# RoverWing-cover-V3_0.net
KiCad netlist of a schematic drawn in EAGLE
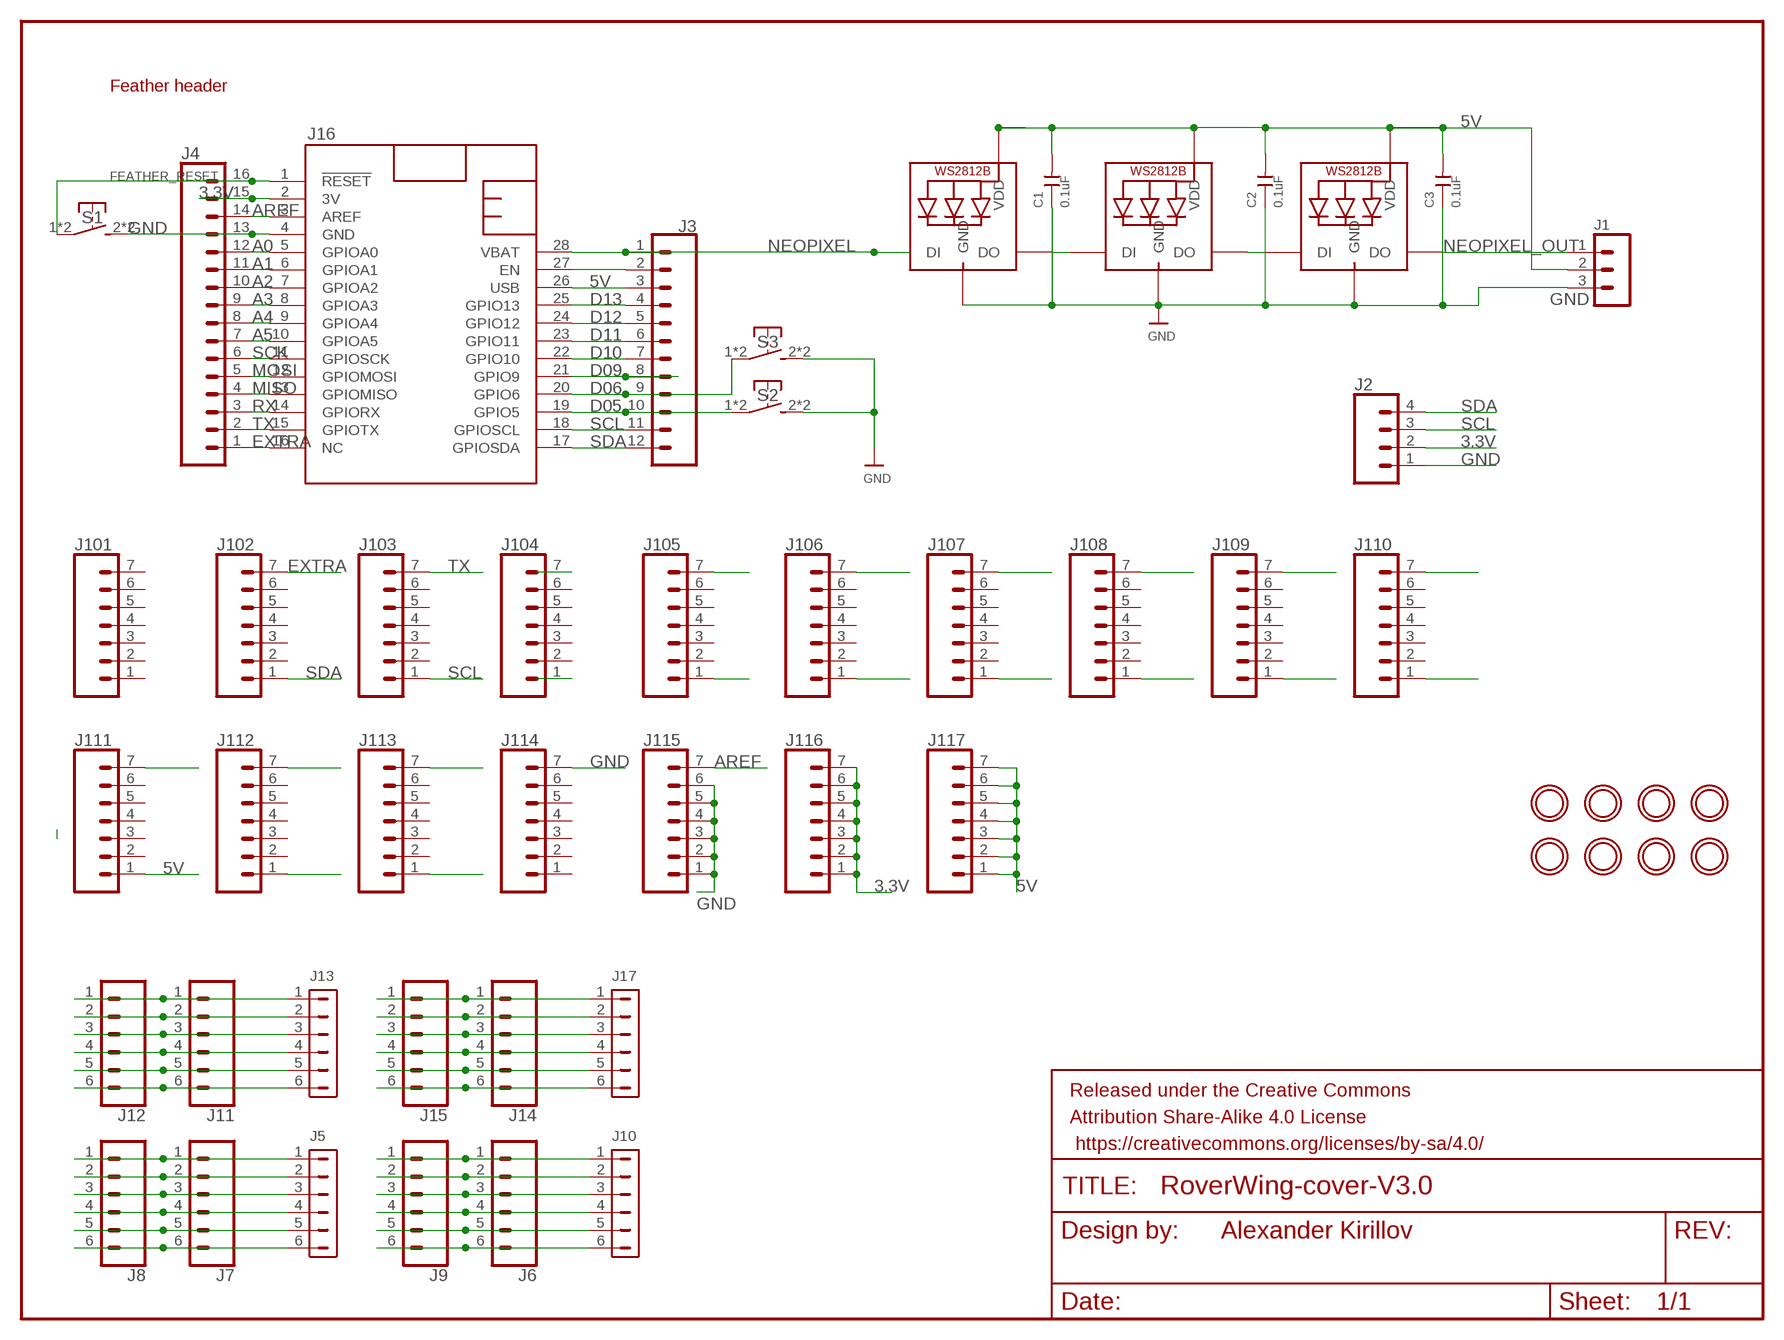
[diagram p0: schematic, sheet 1]

(export (version "E")
  (design (tool "Eeschema 10.0.6"))
  (components
    (comp (ref "C1")
      (value "0.1uF")
      (footprint "eagle-import:0603")
      (fields (field (name "MF") "AVX") (field (name "MPN") "04025C104KAT2A"))
      (libsource (lib "eagle-import") (part "CAP-CERAMIC-SMD0603"))
    )
    (comp (ref "C2")
      (value "0.1uF")
      (footprint "eagle-import:0603")
      (fields (field (name "MF") "AVX") (field (name "MPN") "04025C104KAT2A"))
      (libsource (lib "eagle-import") (part "CAP-CERAMIC-SMD0603"))
    )
    (comp (ref "C3")
      (value "0.1uF")
      (footprint "eagle-import:0603")
      (fields (field (name "MF") "AVX") (field (name "MPN") "04025C104KAT2A"))
      (libsource (lib "eagle-import") (part "CAP-CERAMIC-SMD0603"))
    )
    (comp (ref "FRAME2")
      (value "FRAME-LETTERNO_PACKAGE")
      (footprint "eagle-import:DUMMY")
      (fields (field (name "OC_NEWARK") "unknown") (field (name "DESIGNER") "Nobody"))
      (libsource (lib "eagle-import") (part "FRAME-LETTERNO_PACKAGE"))
    )
    (comp (ref "J1")
      (value "HEADER-PH-3PSIDEENTRY")
      (footprint "eagle-import:S3B-PH-K")
      (fields
        (field (name "PARTNO") "S3B-PH-K-S(LF)(SN)")
        (field (name "MF") "JST (JAPAN SOLDERLESS TERMINALS)")
        (field (name "MPN") "S3B-PH-K-S (LF)(SN)")
      )
      (libsource (lib "eagle-import") (part "HEADER-PH-3PSIDEENTRY"))
    )
    (comp (ref "J2")
      (value "CONN_04")
      (footprint "eagle-import:1X04")
      (libsource (lib "eagle-import") (part "CONN_04"))
    )
    (comp (ref "J3")
      (value "CONN_12NO_SILK")
      (footprint "eagle-import:1X12_NO_SILK")
      (libsource (lib "eagle-import") (part "CONN_12NO_SILK"))
    )
    (comp (ref "J4")
      (value "CONN_161X16_NO_SILK")
      (footprint "eagle-import:1X16_NO_SILK")
      (libsource (lib "eagle-import") (part "CONN_161X16_NO_SILK"))
    )
    (comp (ref "J5")
      (value "HEADER-PH-6PSIDEENTRY")
      (footprint "eagle-import:S6B-PH-K")
      (libsource (lib "eagle-import") (part "HEADER-PH-6PSIDEENTRY"))
    )
    (comp (ref "J6")
      (value "CONN_06NO_SILK_NO_POP")
      (footprint "eagle-import:1X06_NO_SILK")
      (libsource (lib "eagle-import") (part "CONN_06NO_SILK_NO_POP"))
    )
    (comp (ref "J7")
      (value "CONN_06NO_SILK_NO_POP")
      (footprint "eagle-import:1X06_NO_SILK")
      (libsource (lib "eagle-import") (part "CONN_06NO_SILK_NO_POP"))
    )
    (comp (ref "J8")
      (value "CONN_06NO_SILK_NO_POP")
      (footprint "eagle-import:1X06_NO_SILK")
      (libsource (lib "eagle-import") (part "CONN_06NO_SILK_NO_POP"))
    )
    (comp (ref "J9")
      (value "CONN_06NO_SILK_NO_POP")
      (footprint "eagle-import:1X06_NO_SILK")
      (libsource (lib "eagle-import") (part "CONN_06NO_SILK_NO_POP"))
    )
    (comp (ref "J10")
      (value "HEADER-PH-6PSIDEENTRY")
      (footprint "eagle-import:S6B-PH-K")
      (libsource (lib "eagle-import") (part "HEADER-PH-6PSIDEENTRY"))
    )
    (comp (ref "J11")
      (value "CONN_06NO_SILK_NO_POP")
      (footprint "eagle-import:1X06_NO_SILK")
      (libsource (lib "eagle-import") (part "CONN_06NO_SILK_NO_POP"))
    )
    (comp (ref "J12")
      (value "CONN_06NO_SILK_NO_POP")
      (footprint "eagle-import:1X06_NO_SILK")
      (libsource (lib "eagle-import") (part "CONN_06NO_SILK_NO_POP"))
    )
    (comp (ref "J13")
      (value "HEADER-PH-6PSIDEENTRY")
      (footprint "eagle-import:S6B-PH-K")
      (libsource (lib "eagle-import") (part "HEADER-PH-6PSIDEENTRY"))
    )
    (comp (ref "J14")
      (value "CONN_06NO_SILK_NO_POP")
      (footprint "eagle-import:1X06_NO_SILK")
      (libsource (lib "eagle-import") (part "CONN_06NO_SILK_NO_POP"))
    )
    (comp (ref "J15")
      (value "CONN_06NO_SILK_NO_POP")
      (footprint "eagle-import:1X06_NO_SILK")
      (libsource (lib "eagle-import") (part "CONN_06NO_SILK_NO_POP"))
    )
    (comp (ref "J16")
      (value "FEATHERWING_NODIM")
      (footprint "eagle-import:FEATHERWING_DIM")
      (libsource (lib "eagle-import") (part "FEATHERWING_NODIM"))
    )
    (comp (ref "J17")
      (value "HEADER-PH-6PSIDEENTRY")
      (footprint "eagle-import:S6B-PH-K")
      (libsource (lib "eagle-import") (part "HEADER-PH-6PSIDEENTRY"))
    )
    (comp (ref "J101")
      (value "CONN_07NO_SILK")
      (footprint "eagle-import:1X07_NO_SILK")
      (libsource (lib "eagle-import") (part "CONN_07NO_SILK"))
    )
    (comp (ref "J102")
      (value "CONN_07NO_SILK")
      (footprint "eagle-import:1X07_NO_SILK")
      (libsource (lib "eagle-import") (part "CONN_07NO_SILK"))
    )
    (comp (ref "J103")
      (value "CONN_07NO_SILK")
      (footprint "eagle-import:1X07_NO_SILK")
      (libsource (lib "eagle-import") (part "CONN_07NO_SILK"))
    )
    (comp (ref "J104")
      (value "CONN_07NO_SILK")
      (footprint "eagle-import:1X07_NO_SILK")
      (libsource (lib "eagle-import") (part "CONN_07NO_SILK"))
    )
    (comp (ref "J105")
      (value "CONN_07NO_SILK")
      (footprint "eagle-import:1X07_NO_SILK")
      (libsource (lib "eagle-import") (part "CONN_07NO_SILK"))
    )
    (comp (ref "J106")
      (value "CONN_07NO_SILK")
      (footprint "eagle-import:1X07_NO_SILK")
      (libsource (lib "eagle-import") (part "CONN_07NO_SILK"))
    )
    (comp (ref "J107")
      (value "CONN_07NO_SILK")
      (footprint "eagle-import:1X07_NO_SILK")
      (libsource (lib "eagle-import") (part "CONN_07NO_SILK"))
    )
    (comp (ref "J108")
      (value "CONN_07NO_SILK")
      (footprint "eagle-import:1X07_NO_SILK")
      (libsource (lib "eagle-import") (part "CONN_07NO_SILK"))
    )
    (comp (ref "J109")
      (value "CONN_07NO_SILK")
      (footprint "eagle-import:1X07_NO_SILK")
      (libsource (lib "eagle-import") (part "CONN_07NO_SILK"))
    )
    (comp (ref "J110")
      (value "CONN_07NO_SILK")
      (footprint "eagle-import:1X07_NO_SILK")
      (libsource (lib "eagle-import") (part "CONN_07NO_SILK"))
    )
    (comp (ref "J111")
      (value "CONN_07NO_SILK")
      (footprint "eagle-import:1X07_NO_SILK")
      (libsource (lib "eagle-import") (part "CONN_07NO_SILK"))
    )
    (comp (ref "J112")
      (value "CONN_07NO_SILK")
      (footprint "eagle-import:1X07_NO_SILK")
      (libsource (lib "eagle-import") (part "CONN_07NO_SILK"))
    )
    (comp (ref "J113")
      (value "CONN_07NO_SILK")
      (footprint "eagle-import:1X07_NO_SILK")
      (libsource (lib "eagle-import") (part "CONN_07NO_SILK"))
    )
    (comp (ref "J114")
      (value "CONN_07NO_SILK")
      (footprint "eagle-import:1X07_NO_SILK")
      (libsource (lib "eagle-import") (part "CONN_07NO_SILK"))
    )
    (comp (ref "J115")
      (value "CONN_07NO_SILK")
      (footprint "eagle-import:1X07_NO_SILK")
      (libsource (lib "eagle-import") (part "CONN_07NO_SILK"))
    )
    (comp (ref "J116")
      (value "CONN_07NO_SILK")
      (footprint "eagle-import:1X07_NO_SILK")
      (libsource (lib "eagle-import") (part "CONN_07NO_SILK"))
    )
    (comp (ref "J117")
      (value "CONN_07NO_SILK")
      (footprint "eagle-import:1X07_NO_SILK")
      (libsource (lib "eagle-import") (part "CONN_07NO_SILK"))
    )
    (comp (ref "LED1")
      (value "WS2812B3535")
      (footprint "eagle-import:LED3535")
      (fields
        (field (name "MANUFACTURER") "Worldsemi")
        (field (name "PARTNO") "WS2812B-3535 ")
        (field (name "MF") "ADAFRUIT")
      )
      (libsource (lib "eagle-import") (part "WS2812B3535"))
    )
    (comp (ref "LED2")
      (value "WS2812B3535")
      (footprint "eagle-import:LED3535")
      (fields
        (field (name "MANUFACTURER") "Worldsemi")
        (field (name "PARTNO") "WS2812B-3535 ")
        (field (name "MF") "ADAFRUIT")
      )
      (libsource (lib "eagle-import") (part "WS2812B3535"))
    )
    (comp (ref "LED3")
      (value "WS2812B3535")
      (footprint "eagle-import:LED3535")
      (fields
        (field (name "MANUFACTURER") "Worldsemi")
        (field (name "PARTNO") "WS2812B-3535 ")
        (field (name "MF") "ADAFRUIT")
      )
      (libsource (lib "eagle-import") (part "WS2812B3535"))
    )
    (comp (ref "S1")
      (value "SW-TACTILE-4.5X4.5_SMD")
      (footprint "eagle-import:TL3305")
      (fields (field (name "MF") "E-SWITCH") (field (name "MPN") "TL3305AF160QG"))
      (libsource (lib "eagle-import") (part "SW-TACTILE-4.5X4.5_SMD"))
    )
    (comp (ref "S2")
      (value "SW-TACTILE-4.5X4.5_SMD")
      (footprint "eagle-import:TL3305")
      (fields (field (name "MF") "E-SWITCH") (field (name "MPN") "TL3305AF160QG"))
      (libsource (lib "eagle-import") (part "SW-TACTILE-4.5X4.5_SMD"))
    )
    (comp (ref "S3")
      (value "SW-TACTILE-4.5X4.5_SMD")
      (footprint "eagle-import:TL3305")
      (fields (field (name "MF") "E-SWITCH") (field (name "MPN") "TL3305AF160QG"))
      (libsource (lib "eagle-import") (part "SW-TACTILE-4.5X4.5_SMD"))
    )
    (comp (ref "U$3")
      (value "MOUNTINGHOLE3.0_NPH")
      (footprint "eagle-import:MOUNTINGHOLE_3.0_NPH")
      (libsource (lib "eagle-import") (part "MOUNTINGHOLE3.0_NPH"))
    )
    (comp (ref "U$4")
      (value "MOUNTINGHOLE3.0_NPH")
      (footprint "eagle-import:MOUNTINGHOLE_3.0_NPH")
      (libsource (lib "eagle-import") (part "MOUNTINGHOLE3.0_NPH"))
    )
    (comp (ref "U$14")
      (value "MOUNTINGHOLE3.0_NPH")
      (footprint "eagle-import:MOUNTINGHOLE_3.0_NPH")
      (libsource (lib "eagle-import") (part "MOUNTINGHOLE3.0_NPH"))
    )
    (comp (ref "U$15")
      (value "MOUNTINGHOLE3.0_NPH")
      (footprint "eagle-import:MOUNTINGHOLE_3.0_NPH")
      (libsource (lib "eagle-import") (part "MOUNTINGHOLE3.0_NPH"))
    )
    (comp (ref "U$24")
      (value "MOUNTINGHOLE3.0_NPH")
      (footprint "eagle-import:MOUNTINGHOLE_3.0_NPH")
      (libsource (lib "eagle-import") (part "MOUNTINGHOLE3.0_NPH"))
    )
    (comp (ref "U$25")
      (value "MOUNTINGHOLE3.0_NPH")
      (footprint "eagle-import:MOUNTINGHOLE_3.0_NPH")
      (libsource (lib "eagle-import") (part "MOUNTINGHOLE3.0_NPH"))
    )
    (comp (ref "U$26")
      (value "MOUNTINGHOLE3.0_NPH")
      (footprint "eagle-import:MOUNTINGHOLE_3.0_NPH")
      (libsource (lib "eagle-import") (part "MOUNTINGHOLE3.0_NPH"))
    )
    (comp (ref "U$27")
      (value "MOUNTINGHOLE3.0_NPH")
      (footprint "eagle-import:MOUNTINGHOLE_3.0_NPH")
      (libsource (lib "eagle-import") (part "MOUNTINGHOLE3.0_NPH"))
    )
  )
  (nets
    (net (code "1") (name "/3.3V") (class "Default")
      (node (ref "J116") (pin "1") (pinfunction "1_1") (pintype "passive"))
      (node (ref "J116") (pin "2") (pinfunction "2_2") (pintype "passive"))
      (node (ref "J116") (pin "3") (pinfunction "3_3") (pintype "passive"))
      (node (ref "J116") (pin "4") (pinfunction "4_4") (pintype "passive"))
      (node (ref "J116") (pin "5") (pinfunction "5_5") (pintype "passive"))
      (node (ref "J116") (pin "6") (pinfunction "6_6") (pintype "passive"))
      (node (ref "J116") (pin "7") (pinfunction "7_7") (pintype "passive"))
      (node (ref "J16") (pin "2") (pinfunction "3V_2") (pintype "power_in"))
      (node (ref "J2") (pin "2") (pinfunction "2_2") (pintype "passive"))
      (node (ref "J4") (pin "15") (pinfunction "15_15") (pintype "passive"))
    )
    (net (code "2") (name "/5V") (class "Default")
      (node (ref "C1") (pin "2") (pinfunction "2_2") (pintype "passive"))
      (node (ref "C2") (pin "2") (pinfunction "2_2") (pintype "passive"))
      (node (ref "C3") (pin "2") (pinfunction "2_2") (pintype "passive"))
      (node (ref "J1") (pin "2") (pinfunction "2_2") (pintype "passive"))
      (node (ref "J111") (pin "1") (pinfunction "1_1") (pintype "passive"))
      (node (ref "J117") (pin "1") (pinfunction "1_1") (pintype "passive"))
      (node (ref "J117") (pin "2") (pinfunction "2_2") (pintype "passive"))
      (node (ref "J117") (pin "3") (pinfunction "3_3") (pintype "passive"))
      (node (ref "J117") (pin "4") (pinfunction "4_4") (pintype "passive"))
      (node (ref "J117") (pin "5") (pinfunction "5_5") (pintype "passive"))
      (node (ref "J117") (pin "6") (pinfunction "6_6") (pintype "passive"))
      (node (ref "J117") (pin "7") (pinfunction "7_7") (pintype "passive"))
      (node (ref "J16") (pin "26") (pinfunction "USB_26") (pintype "power_in"))
      (node (ref "J3") (pin "3") (pinfunction "3_3") (pintype "passive"))
      (node (ref "LED1") (pin "3") (pinfunction "VDD_3") (pintype "power_in"))
      (node (ref "LED2") (pin "3") (pinfunction "VDD_3") (pintype "power_in"))
      (node (ref "LED3") (pin "3") (pinfunction "VDD_3") (pintype "power_in"))
    )
    (net (code "3") (name "/A0") (class "Default")
      (node (ref "J113") (pin "7") (pinfunction "7_7") (pintype "passive"))
      (node (ref "J16") (pin "5") (pinfunction "GPIOA0_5") (pintype "bidirectional"))
      (node (ref "J4") (pin "12") (pinfunction "12_12") (pintype "passive"))
    )
    (net (code "4") (name "/A1") (class "Default")
      (node (ref "J112") (pin "7") (pinfunction "7_7") (pintype "passive"))
      (node (ref "J16") (pin "6") (pinfunction "GPIOA1_6") (pintype "bidirectional"))
      (node (ref "J4") (pin "11") (pinfunction "11_11") (pintype "passive"))
    )
    (net (code "5") (name "/A2") (class "Default")
      (node (ref "J111") (pin "7") (pinfunction "7_7") (pintype "passive"))
      (node (ref "J16") (pin "7") (pinfunction "GPIOA2_7") (pintype "bidirectional"))
      (node (ref "J4") (pin "10") (pinfunction "10_10") (pintype "passive"))
    )
    (net (code "6") (name "/A3") (class "Default")
      (node (ref "J110") (pin "7") (pinfunction "7_7") (pintype "passive"))
      (node (ref "J16") (pin "8") (pinfunction "GPIOA3_8") (pintype "bidirectional"))
      (node (ref "J4") (pin "9") (pinfunction "9_9") (pintype "passive"))
    )
    (net (code "7") (name "/A4") (class "Default")
      (node (ref "J109") (pin "7") (pinfunction "7_7") (pintype "passive"))
      (node (ref "J16") (pin "9") (pinfunction "GPIOA4_9") (pintype "bidirectional"))
      (node (ref "J4") (pin "8") (pinfunction "8_8") (pintype "passive"))
    )
    (net (code "8") (name "/A5") (class "Default")
      (node (ref "J108") (pin "7") (pinfunction "7_7") (pintype "passive"))
      (node (ref "J16") (pin "10") (pinfunction "GPIOA5_10") (pintype "bidirectional"))
      (node (ref "J4") (pin "7") (pinfunction "7_7") (pintype "passive"))
    )
    (net (code "9") (name "/AREF") (class "Default")
      (node (ref "J115") (pin "7") (pinfunction "7_7") (pintype "passive"))
      (node (ref "J16") (pin "3") (pinfunction "AREF_3") (pintype "passive"))
      (node (ref "J4") (pin "14") (pinfunction "14_14") (pintype "passive"))
    )
    (net (code "10") (name "/D05") (class "Default")
      (node (ref "J104") (pin "1") (pinfunction "1_1") (pintype "passive"))
      (node (ref "J16") (pin "19") (pinfunction "GPIO5_19") (pintype "bidirectional"))
      (node (ref "J3") (pin "10") (pinfunction "10_10") (pintype "passive"))
      (node (ref "S2") (pin "1") (pinfunction "P1_1") (pintype "passive"))
      (node (ref "S2") (pin "4") (pinfunction "P1_4") (pintype "passive"))
    )
    (net (code "11") (name "/D06") (class "Default")
      (node (ref "J105") (pin "1") (pinfunction "1_1") (pintype "passive"))
      (node (ref "J16") (pin "20") (pinfunction "GPIO6_20") (pintype "bidirectional"))
      (node (ref "J3") (pin "9") (pinfunction "9_9") (pintype "passive"))
      (node (ref "S3") (pin "1") (pinfunction "P1_1") (pintype "passive"))
      (node (ref "S3") (pin "4") (pinfunction "P1_4") (pintype "passive"))
    )
    (net (code "12") (name "/D09") (class "Default")
      (node (ref "J106") (pin "1") (pinfunction "1_1") (pintype "passive"))
      (node (ref "J16") (pin "21") (pinfunction "GPIO9_21") (pintype "bidirectional"))
      (node (ref "J3") (pin "8") (pinfunction "8_8") (pintype "passive"))
    )
    (net (code "13") (name "/D10") (class "Default")
      (node (ref "J107") (pin "1") (pinfunction "1_1") (pintype "passive"))
      (node (ref "J16") (pin "22") (pinfunction "GPIO10_22") (pintype "bidirectional"))
      (node (ref "J3") (pin "7") (pinfunction "7_7") (pintype "passive"))
    )
    (net (code "14") (name "/D11") (class "Default")
      (node (ref "J108") (pin "1") (pinfunction "1_1") (pintype "passive"))
      (node (ref "J16") (pin "23") (pinfunction "GPIO11_23") (pintype "bidirectional"))
      (node (ref "J3") (pin "6") (pinfunction "6_6") (pintype "passive"))
    )
    (net (code "15") (name "/D12") (class "Default")
      (node (ref "J109") (pin "1") (pinfunction "1_1") (pintype "passive"))
      (node (ref "J16") (pin "24") (pinfunction "GPIO12_24") (pintype "bidirectional"))
      (node (ref "J3") (pin "5") (pinfunction "5_5") (pintype "passive"))
    )
    (net (code "16") (name "/D13") (class "Default")
      (node (ref "J110") (pin "1") (pinfunction "1_1") (pintype "passive"))
      (node (ref "J16") (pin "25") (pinfunction "GPIO13_25") (pintype "bidirectional"))
      (node (ref "J3") (pin "4") (pinfunction "4_4") (pintype "passive"))
    )
    (net (code "17") (name "/EXTRA") (class "Default")
      (node (ref "J102") (pin "7") (pinfunction "7_7") (pintype "passive"))
      (node (ref "J16") (pin "16") (pinfunction "NC_16") (pintype "passive"))
      (node (ref "J4") (pin "1") (pinfunction "1_1") (pintype "passive"))
    )
    (net (code "18") (name "/FEATHER_RESET") (class "Default")
      (node (ref "J16") (pin "1") (pinfunction "~{RESET}_1") (pintype "input"))
      (node (ref "J4") (pin "16") (pinfunction "16_16") (pintype "passive"))
      (node (ref "S1") (pin "1") (pinfunction "P1_1") (pintype "passive"))
      (node (ref "S1") (pin "4") (pinfunction "P1_4") (pintype "passive"))
    )
    (net (code "19") (name "/MISO") (class "Default")
      (node (ref "J105") (pin "7") (pinfunction "7_7") (pintype "passive"))
      (node (ref "J16") (pin "13") (pinfunction "GPIOMISO_13") (pintype "bidirectional"))
      (node (ref "J4") (pin "4") (pinfunction "4_4") (pintype "passive"))
    )
    (net (code "20") (name "/MOSI") (class "Default")
      (node (ref "J106") (pin "7") (pinfunction "7_7") (pintype "passive"))
      (node (ref "J16") (pin "12") (pinfunction "GPIOMOSI_12") (pintype "bidirectional"))
      (node (ref "J4") (pin "5") (pinfunction "5_5") (pintype "passive"))
    )
    (net (code "21") (name "/N$37") (class "Default")
      (node (ref "J112") (pin "1") (pinfunction "1_1") (pintype "passive"))
      (node (ref "J16") (pin "27") (pinfunction "EN_27") (pintype "passive"))
      (node (ref "J3") (pin "2") (pinfunction "2_2") (pintype "passive"))
    )
    (net (code "22") (name "/NEOPIXEL") (class "Default")
      (node (ref "J16") (pin "28") (pinfunction "VBAT_28") (pintype "power_in"))
      (node (ref "J3") (pin "1") (pinfunction "1_1") (pintype "passive"))
      (node (ref "LED1") (pin "2") (pinfunction "DI_2") (pintype "input"))
    )
    (net (code "23") (name "/NEOPIXEL_OUT") (class "Default")
      (node (ref "J1") (pin "1") (pinfunction "1_1") (pintype "passive"))
      (node (ref "LED3") (pin "4") (pinfunction "DO_4") (pintype "output"))
    )
    (net (code "24") (name "/RX") (class "Default")
      (node (ref "J104") (pin "7") (pinfunction "7_7") (pintype "passive"))
      (node (ref "J16") (pin "14") (pinfunction "GPIORX_14") (pintype "bidirectional"))
      (node (ref "J4") (pin "3") (pinfunction "3_3") (pintype "passive"))
    )
    (net (code "25") (name "/SCK") (class "Default")
      (node (ref "J107") (pin "7") (pinfunction "7_7") (pintype "passive"))
      (node (ref "J16") (pin "11") (pinfunction "GPIOSCK_11") (pintype "bidirectional"))
      (node (ref "J4") (pin "6") (pinfunction "6_6") (pintype "passive"))
    )
    (net (code "26") (name "/SCL") (class "Default")
      (node (ref "J103") (pin "1") (pinfunction "1_1") (pintype "passive"))
      (node (ref "J16") (pin "18") (pinfunction "GPIOSCL_18") (pintype "bidirectional"))
      (node (ref "J2") (pin "3") (pinfunction "3_3") (pintype "passive"))
      (node (ref "J3") (pin "11") (pinfunction "11_11") (pintype "passive"))
    )
    (net (code "27") (name "/SDA") (class "Default")
      (node (ref "J102") (pin "1") (pinfunction "1_1") (pintype "passive"))
      (node (ref "J16") (pin "17") (pinfunction "GPIOSDA_17") (pintype "bidirectional"))
      (node (ref "J2") (pin "4") (pinfunction "4_4") (pintype "passive"))
      (node (ref "J3") (pin "12") (pinfunction "12_12") (pintype "passive"))
    )
    (net (code "28") (name "/TX") (class "Default")
      (node (ref "J103") (pin "7") (pinfunction "7_7") (pintype "passive"))
      (node (ref "J16") (pin "15") (pinfunction "GPIOTX_15") (pintype "bidirectional"))
      (node (ref "J4") (pin "2") (pinfunction "2_2") (pintype "passive"))
    )
    (net (code "29") (name "GND") (class "Default")
      (node (ref "C1") (pin "1") (pinfunction "1_1") (pintype "passive"))
      (node (ref "C2") (pin "1") (pinfunction "1_1") (pintype "passive"))
      (node (ref "C3") (pin "1") (pinfunction "1_1") (pintype "passive"))
      (node (ref "J1") (pin "3") (pinfunction "3_3") (pintype "passive"))
      (node (ref "J114") (pin "7") (pinfunction "7_7") (pintype "passive"))
      (node (ref "J115") (pin "1") (pinfunction "1_1") (pintype "passive"))
      (node (ref "J115") (pin "2") (pinfunction "2_2") (pintype "passive"))
      (node (ref "J115") (pin "3") (pinfunction "3_3") (pintype "passive"))
      (node (ref "J115") (pin "4") (pinfunction "4_4") (pintype "passive"))
      (node (ref "J115") (pin "5") (pinfunction "5_5") (pintype "passive"))
      (node (ref "J115") (pin "6") (pinfunction "6_6") (pintype "passive"))
      (node (ref "J16") (pin "4") (pinfunction "GND_4") (pintype "power_in"))
      (node (ref "J2") (pin "1") (pinfunction "1_1") (pintype "passive"))
      (node (ref "J4") (pin "13") (pinfunction "13_13") (pintype "passive"))
      (node (ref "LED1") (pin "1") (pinfunction "GND_1") (pintype "power_in"))
      (node (ref "LED2") (pin "1") (pinfunction "GND_1") (pintype "power_in"))
      (node (ref "LED3") (pin "1") (pinfunction "GND_1") (pintype "power_in"))
      (node (ref "S1") (pin "2") (pinfunction "S1_2") (pintype "passive"))
      (node (ref "S1") (pin "3") (pinfunction "S1_3") (pintype "passive"))
      (node (ref "S2") (pin "2") (pinfunction "S1_2") (pintype "passive"))
      (node (ref "S2") (pin "3") (pinfunction "S1_3") (pintype "passive"))
      (node (ref "S3") (pin "2") (pinfunction "S1_2") (pintype "passive"))
      (node (ref "S3") (pin "3") (pinfunction "S1_3") (pintype "passive"))
    )
    (net (code "30") (name "Net-(J5-Pad1)") (class "Default")
      (node (ref "J5") (pin "1") (pinfunction "1_1") (pintype "passive"))
      (node (ref "J7") (pin "1") (pinfunction "1_1") (pintype "passive"))
      (node (ref "J8") (pin "1") (pinfunction "1_1") (pintype "passive"))
    )
    (net (code "31") (name "Net-(J5-Pad2)") (class "Default")
      (node (ref "J5") (pin "2") (pinfunction "2_2") (pintype "passive"))
      (node (ref "J7") (pin "2") (pinfunction "2_2") (pintype "passive"))
      (node (ref "J8") (pin "2") (pinfunction "2_2") (pintype "passive"))
    )
    (net (code "32") (name "Net-(J5-Pad3)") (class "Default")
      (node (ref "J5") (pin "3") (pinfunction "3_3") (pintype "passive"))
      (node (ref "J7") (pin "3") (pinfunction "3_3") (pintype "passive"))
      (node (ref "J8") (pin "3") (pinfunction "3_3") (pintype "passive"))
    )
    (net (code "33") (name "Net-(J5-Pad4)") (class "Default")
      (node (ref "J5") (pin "4") (pinfunction "4_4") (pintype "passive"))
      (node (ref "J7") (pin "4") (pinfunction "4_4") (pintype "passive"))
      (node (ref "J8") (pin "4") (pinfunction "4_4") (pintype "passive"))
    )
    (net (code "34") (name "Net-(J5-Pad5)") (class "Default")
      (node (ref "J5") (pin "5") (pinfunction "5_5") (pintype "passive"))
      (node (ref "J7") (pin "5") (pinfunction "5_5") (pintype "passive"))
      (node (ref "J8") (pin "5") (pinfunction "5_5") (pintype "passive"))
    )
    (net (code "35") (name "Net-(J5-Pad6)") (class "Default")
      (node (ref "J5") (pin "6") (pinfunction "6_6") (pintype "passive"))
      (node (ref "J7") (pin "6") (pinfunction "6_6") (pintype "passive"))
      (node (ref "J8") (pin "6") (pinfunction "6_6") (pintype "passive"))
    )
    (net (code "36") (name "Net-(J10-Pad1)") (class "Default")
      (node (ref "J10") (pin "1") (pinfunction "1_1") (pintype "passive"))
      (node (ref "J6") (pin "1") (pinfunction "1_1") (pintype "passive"))
      (node (ref "J9") (pin "1") (pinfunction "1_1") (pintype "passive"))
    )
    (net (code "37") (name "Net-(J10-Pad2)") (class "Default")
      (node (ref "J10") (pin "2") (pinfunction "2_2") (pintype "passive"))
      (node (ref "J6") (pin "2") (pinfunction "2_2") (pintype "passive"))
      (node (ref "J9") (pin "2") (pinfunction "2_2") (pintype "passive"))
    )
    (net (code "38") (name "Net-(J10-Pad3)") (class "Default")
      (node (ref "J10") (pin "3") (pinfunction "3_3") (pintype "passive"))
      (node (ref "J6") (pin "3") (pinfunction "3_3") (pintype "passive"))
      (node (ref "J9") (pin "3") (pinfunction "3_3") (pintype "passive"))
    )
    (net (code "39") (name "Net-(J10-Pad4)") (class "Default")
      (node (ref "J10") (pin "4") (pinfunction "4_4") (pintype "passive"))
      (node (ref "J6") (pin "4") (pinfunction "4_4") (pintype "passive"))
      (node (ref "J9") (pin "4") (pinfunction "4_4") (pintype "passive"))
    )
    (net (code "40") (name "Net-(J10-Pad5)") (class "Default")
      (node (ref "J10") (pin "5") (pinfunction "5_5") (pintype "passive"))
      (node (ref "J6") (pin "5") (pinfunction "5_5") (pintype "passive"))
      (node (ref "J9") (pin "5") (pinfunction "5_5") (pintype "passive"))
    )
    (net (code "41") (name "Net-(J10-Pad6)") (class "Default")
      (node (ref "J10") (pin "6") (pinfunction "6_6") (pintype "passive"))
      (node (ref "J6") (pin "6") (pinfunction "6_6") (pintype "passive"))
      (node (ref "J9") (pin "6") (pinfunction "6_6") (pintype "passive"))
    )
    (net (code "42") (name "Net-(J11-Pad1)") (class "Default")
      (node (ref "J11") (pin "1") (pinfunction "1_1") (pintype "passive"))
      (node (ref "J12") (pin "1") (pinfunction "1_1") (pintype "passive"))
      (node (ref "J13") (pin "1") (pinfunction "1_1") (pintype "passive"))
    )
    (net (code "43") (name "Net-(J11-Pad2)") (class "Default")
      (node (ref "J11") (pin "2") (pinfunction "2_2") (pintype "passive"))
      (node (ref "J12") (pin "2") (pinfunction "2_2") (pintype "passive"))
      (node (ref "J13") (pin "2") (pinfunction "2_2") (pintype "passive"))
    )
    (net (code "44") (name "Net-(J11-Pad3)") (class "Default")
      (node (ref "J11") (pin "3") (pinfunction "3_3") (pintype "passive"))
      (node (ref "J12") (pin "3") (pinfunction "3_3") (pintype "passive"))
      (node (ref "J13") (pin "3") (pinfunction "3_3") (pintype "passive"))
    )
    (net (code "45") (name "Net-(J11-Pad4)") (class "Default")
      (node (ref "J11") (pin "4") (pinfunction "4_4") (pintype "passive"))
      (node (ref "J12") (pin "4") (pinfunction "4_4") (pintype "passive"))
      (node (ref "J13") (pin "4") (pinfunction "4_4") (pintype "passive"))
    )
    (net (code "46") (name "Net-(J11-Pad5)") (class "Default")
      (node (ref "J11") (pin "5") (pinfunction "5_5") (pintype "passive"))
      (node (ref "J12") (pin "5") (pinfunction "5_5") (pintype "passive"))
      (node (ref "J13") (pin "5") (pinfunction "5_5") (pintype "passive"))
    )
    (net (code "47") (name "Net-(J11-Pad6)") (class "Default")
      (node (ref "J11") (pin "6") (pinfunction "6_6") (pintype "passive"))
      (node (ref "J12") (pin "6") (pinfunction "6_6") (pintype "passive"))
      (node (ref "J13") (pin "6") (pinfunction "6_6") (pintype "passive"))
    )
    (net (code "48") (name "Net-(J14-Pad1)") (class "Default")
      (node (ref "J14") (pin "1") (pinfunction "1_1") (pintype "passive"))
      (node (ref "J15") (pin "1") (pinfunction "1_1") (pintype "passive"))
      (node (ref "J17") (pin "1") (pinfunction "1_1") (pintype "passive"))
    )
    (net (code "49") (name "Net-(J14-Pad2)") (class "Default")
      (node (ref "J14") (pin "2") (pinfunction "2_2") (pintype "passive"))
      (node (ref "J15") (pin "2") (pinfunction "2_2") (pintype "passive"))
      (node (ref "J17") (pin "2") (pinfunction "2_2") (pintype "passive"))
    )
    (net (code "50") (name "Net-(J14-Pad3)") (class "Default")
      (node (ref "J14") (pin "3") (pinfunction "3_3") (pintype "passive"))
      (node (ref "J15") (pin "3") (pinfunction "3_3") (pintype "passive"))
      (node (ref "J17") (pin "3") (pinfunction "3_3") (pintype "passive"))
    )
    (net (code "51") (name "Net-(J14-Pad4)") (class "Default")
      (node (ref "J14") (pin "4") (pinfunction "4_4") (pintype "passive"))
      (node (ref "J15") (pin "4") (pinfunction "4_4") (pintype "passive"))
      (node (ref "J17") (pin "4") (pinfunction "4_4") (pintype "passive"))
    )
    (net (code "52") (name "Net-(J14-Pad5)") (class "Default")
      (node (ref "J14") (pin "5") (pinfunction "5_5") (pintype "passive"))
      (node (ref "J15") (pin "5") (pinfunction "5_5") (pintype "passive"))
      (node (ref "J17") (pin "5") (pinfunction "5_5") (pintype "passive"))
    )
    (net (code "53") (name "Net-(J14-Pad6)") (class "Default")
      (node (ref "J14") (pin "6") (pinfunction "6_6") (pintype "passive"))
      (node (ref "J15") (pin "6") (pinfunction "6_6") (pintype "passive"))
      (node (ref "J17") (pin "6") (pinfunction "6_6") (pintype "passive"))
    )
    (net (code "54") (name "Net-(LED1-DO)") (class "Default")
      (node (ref "LED1") (pin "4") (pinfunction "DO_4") (pintype "output"))
      (node (ref "LED2") (pin "2") (pinfunction "DI_2") (pintype "input"))
    )
    (net (code "55") (name "Net-(LED2-DO)") (class "Default")
      (node (ref "LED2") (pin "4") (pinfunction "DO_4") (pintype "output"))
      (node (ref "LED3") (pin "2") (pinfunction "DI_2") (pintype "input"))
    )
    (net (code "56") (name "unconnected-(J101-Pad1)") (class "Default")
      (node (ref "J101") (pin "1") (pinfunction "1_1") (pintype "passive"))
    )
    (net (code "57") (name "unconnected-(J101-Pad2)") (class "Default")
      (node (ref "J101") (pin "2") (pinfunction "2_2") (pintype "passive"))
    )
    (net (code "58") (name "unconnected-(J101-Pad3)") (class "Default")
      (node (ref "J101") (pin "3") (pinfunction "3_3") (pintype "passive"))
    )
    (net (code "59") (name "unconnected-(J101-Pad4)") (class "Default")
      (node (ref "J101") (pin "4") (pinfunction "4_4") (pintype "passive"))
    )
    (net (code "60") (name "unconnected-(J101-Pad5)") (class "Default")
      (node (ref "J101") (pin "5") (pinfunction "5_5") (pintype "passive"))
    )
    (net (code "61") (name "unconnected-(J101-Pad6)") (class "Default")
      (node (ref "J101") (pin "6") (pinfunction "6_6") (pintype "passive"))
    )
    (net (code "62") (name "unconnected-(J101-Pad7)") (class "Default")
      (node (ref "J101") (pin "7") (pinfunction "7_7") (pintype "passive"))
    )
    (net (code "63") (name "unconnected-(J102-Pad2)") (class "Default")
      (node (ref "J102") (pin "2") (pinfunction "2_2") (pintype "passive"))
    )
    (net (code "64") (name "unconnected-(J102-Pad3)") (class "Default")
      (node (ref "J102") (pin "3") (pinfunction "3_3") (pintype "passive"))
    )
    (net (code "65") (name "unconnected-(J102-Pad4)") (class "Default")
      (node (ref "J102") (pin "4") (pinfunction "4_4") (pintype "passive"))
    )
    (net (code "66") (name "unconnected-(J102-Pad5)") (class "Default")
      (node (ref "J102") (pin "5") (pinfunction "5_5") (pintype "passive"))
    )
    (net (code "67") (name "unconnected-(J102-Pad6)") (class "Default")
      (node (ref "J102") (pin "6") (pinfunction "6_6") (pintype "passive"))
    )
    (net (code "68") (name "unconnected-(J103-Pad2)") (class "Default")
      (node (ref "J103") (pin "2") (pinfunction "2_2") (pintype "passive"))
    )
    (net (code "69") (name "unconnected-(J103-Pad3)") (class "Default")
      (node (ref "J103") (pin "3") (pinfunction "3_3") (pintype "passive"))
    )
    (net (code "70") (name "unconnected-(J103-Pad4)") (class "Default")
      (node (ref "J103") (pin "4") (pinfunction "4_4") (pintype "passive"))
    )
    (net (code "71") (name "unconnected-(J103-Pad5)") (class "Default")
      (node (ref "J103") (pin "5") (pinfunction "5_5") (pintype "passive"))
    )
    (net (code "72") (name "unconnected-(J103-Pad6)") (class "Default")
      (node (ref "J103") (pin "6") (pinfunction "6_6") (pintype "passive"))
    )
    (net (code "73") (name "unconnected-(J104-Pad2)") (class "Default")
      (node (ref "J104") (pin "2") (pinfunction "2_2") (pintype "passive"))
    )
    (net (code "74") (name "unconnected-(J104-Pad3)") (class "Default")
      (node (ref "J104") (pin "3") (pinfunction "3_3") (pintype "passive"))
    )
    (net (code "75") (name "unconnected-(J104-Pad4)") (class "Default")
      (node (ref "J104") (pin "4") (pinfunction "4_4") (pintype "passive"))
    )
    (net (code "76") (name "unconnected-(J104-Pad5)") (class "Default")
      (node (ref "J104") (pin "5") (pinfunction "5_5") (pintype "passive"))
    )
    (net (code "77") (name "unconnected-(J104-Pad6)") (class "Default")
      (node (ref "J104") (pin "6") (pinfunction "6_6") (pintype "passive"))
    )
    (net (code "78") (name "unconnected-(J105-Pad2)") (class "Default")
      (node (ref "J105") (pin "2") (pinfunction "2_2") (pintype "passive"))
    )
    (net (code "79") (name "unconnected-(J105-Pad3)") (class "Default")
      (node (ref "J105") (pin "3") (pinfunction "3_3") (pintype "passive"))
    )
    (net (code "80") (name "unconnected-(J105-Pad4)") (class "Default")
      (node (ref "J105") (pin "4") (pinfunction "4_4") (pintype "passive"))
    )
    (net (code "81") (name "unconnected-(J105-Pad5)") (class "Default")
      (node (ref "J105") (pin "5") (pinfunction "5_5") (pintype "passive"))
    )
    (net (code "82") (name "unconnected-(J105-Pad6)") (class "Default")
      (node (ref "J105") (pin "6") (pinfunction "6_6") (pintype "passive"))
    )
    (net (code "83") (name "unconnected-(J106-Pad2)") (class "Default")
      (node (ref "J106") (pin "2") (pinfunction "2_2") (pintype "passive"))
    )
    (net (code "84") (name "unconnected-(J106-Pad3)") (class "Default")
      (node (ref "J106") (pin "3") (pinfunction "3_3") (pintype "passive"))
    )
    (net (code "85") (name "unconnected-(J106-Pad4)") (class "Default")
      (node (ref "J106") (pin "4") (pinfunction "4_4") (pintype "passive"))
    )
    (net (code "86") (name "unconnected-(J106-Pad5)") (class "Default")
      (node (ref "J106") (pin "5") (pinfunction "5_5") (pintype "passive"))
    )
    (net (code "87") (name "unconnected-(J106-Pad6)") (class "Default")
      (node (ref "J106") (pin "6") (pinfunction "6_6") (pintype "passive"))
    )
    (net (code "88") (name "unconnected-(J107-Pad2)") (class "Default")
      (node (ref "J107") (pin "2") (pinfunction "2_2") (pintype "passive"))
    )
    (net (code "89") (name "unconnected-(J107-Pad3)") (class "Default")
      (node (ref "J107") (pin "3") (pinfunction "3_3") (pintype "passive"))
    )
    (net (code "90") (name "unconnected-(J107-Pad4)") (class "Default")
      (node (ref "J107") (pin "4") (pinfunction "4_4") (pintype "passive"))
    )
    (net (code "91") (name "unconnected-(J107-Pad5)") (class "Default")
      (node (ref "J107") (pin "5") (pinfunction "5_5") (pintype "passive"))
    )
    (net (code "92") (name "unconnected-(J107-Pad6)") (class "Default")
      (node (ref "J107") (pin "6") (pinfunction "6_6") (pintype "passive"))
    )
    (net (code "93") (name "unconnected-(J108-Pad2)") (class "Default")
      (node (ref "J108") (pin "2") (pinfunction "2_2") (pintype "passive"))
    )
    (net (code "94") (name "unconnected-(J108-Pad3)") (class "Default")
      (node (ref "J108") (pin "3") (pinfunction "3_3") (pintype "passive"))
    )
    (net (code "95") (name "unconnected-(J108-Pad4)") (class "Default")
      (node (ref "J108") (pin "4") (pinfunction "4_4") (pintype "passive"))
    )
    (net (code "96") (name "unconnected-(J108-Pad5)") (class "Default")
      (node (ref "J108") (pin "5") (pinfunction "5_5") (pintype "passive"))
    )
    (net (code "97") (name "unconnected-(J108-Pad6)") (class "Default")
      (node (ref "J108") (pin "6") (pinfunction "6_6") (pintype "passive"))
    )
    (net (code "98") (name "unconnected-(J109-Pad2)") (class "Default")
      (node (ref "J109") (pin "2") (pinfunction "2_2") (pintype "passive"))
    )
    (net (code "99") (name "unconnected-(J109-Pad3)") (class "Default")
      (node (ref "J109") (pin "3") (pinfunction "3_3") (pintype "passive"))
    )
    (net (code "100") (name "unconnected-(J109-Pad4)") (class "Default")
      (node (ref "J109") (pin "4") (pinfunction "4_4") (pintype "passive"))
    )
    (net (code "101") (name "unconnected-(J109-Pad5)") (class "Default")
      (node (ref "J109") (pin "5") (pinfunction "5_5") (pintype "passive"))
    )
    (net (code "102") (name "unconnected-(J109-Pad6)") (class "Default")
      (node (ref "J109") (pin "6") (pinfunction "6_6") (pintype "passive"))
    )
    (net (code "103") (name "unconnected-(J110-Pad2)") (class "Default")
      (node (ref "J110") (pin "2") (pinfunction "2_2") (pintype "passive"))
    )
    (net (code "104") (name "unconnected-(J110-Pad3)") (class "Default")
      (node (ref "J110") (pin "3") (pinfunction "3_3") (pintype "passive"))
    )
    (net (code "105") (name "unconnected-(J110-Pad4)") (class "Default")
      (node (ref "J110") (pin "4") (pinfunction "4_4") (pintype "passive"))
    )
    (net (code "106") (name "unconnected-(J110-Pad5)") (class "Default")
      (node (ref "J110") (pin "5") (pinfunction "5_5") (pintype "passive"))
    )
    (net (code "107") (name "unconnected-(J110-Pad6)") (class "Default")
      (node (ref "J110") (pin "6") (pinfunction "6_6") (pintype "passive"))
    )
    (net (code "108") (name "unconnected-(J111-Pad2)") (class "Default")
      (node (ref "J111") (pin "2") (pinfunction "2_2") (pintype "passive"))
    )
    (net (code "109") (name "unconnected-(J111-Pad3)") (class "Default")
      (node (ref "J111") (pin "3") (pinfunction "3_3") (pintype "passive"))
    )
    (net (code "110") (name "unconnected-(J111-Pad4)") (class "Default")
      (node (ref "J111") (pin "4") (pinfunction "4_4") (pintype "passive"))
    )
    (net (code "111") (name "unconnected-(J111-Pad5)") (class "Default")
      (node (ref "J111") (pin "5") (pinfunction "5_5") (pintype "passive"))
    )
    (net (code "112") (name "unconnected-(J111-Pad6)") (class "Default")
      (node (ref "J111") (pin "6") (pinfunction "6_6") (pintype "passive"))
    )
    (net (code "113") (name "unconnected-(J112-Pad2)") (class "Default")
      (node (ref "J112") (pin "2") (pinfunction "2_2") (pintype "passive"))
    )
    (net (code "114") (name "unconnected-(J112-Pad3)") (class "Default")
      (node (ref "J112") (pin "3") (pinfunction "3_3") (pintype "passive"))
    )
    (net (code "115") (name "unconnected-(J112-Pad4)") (class "Default")
      (node (ref "J112") (pin "4") (pinfunction "4_4") (pintype "passive"))
    )
    (net (code "116") (name "unconnected-(J112-Pad5)") (class "Default")
      (node (ref "J112") (pin "5") (pinfunction "5_5") (pintype "passive"))
    )
    (net (code "117") (name "unconnected-(J112-Pad6)") (class "Default")
      (node (ref "J112") (pin "6") (pinfunction "6_6") (pintype "passive"))
    )
    (net (code "118") (name "unconnected-(J113-Pad1)") (class "Default")
      (node (ref "J113") (pin "1") (pinfunction "1_1") (pintype "passive"))
    )
    (net (code "119") (name "unconnected-(J113-Pad2)") (class "Default")
      (node (ref "J113") (pin "2") (pinfunction "2_2") (pintype "passive"))
    )
    (net (code "120") (name "unconnected-(J113-Pad3)") (class "Default")
      (node (ref "J113") (pin "3") (pinfunction "3_3") (pintype "passive"))
    )
    (net (code "121") (name "unconnected-(J113-Pad4)") (class "Default")
      (node (ref "J113") (pin "4") (pinfunction "4_4") (pintype "passive"))
    )
    (net (code "122") (name "unconnected-(J113-Pad5)") (class "Default")
      (node (ref "J113") (pin "5") (pinfunction "5_5") (pintype "passive"))
    )
    (net (code "123") (name "unconnected-(J113-Pad6)") (class "Default")
      (node (ref "J113") (pin "6") (pinfunction "6_6") (pintype "passive"))
    )
    (net (code "124") (name "unconnected-(J114-Pad1)") (class "Default")
      (node (ref "J114") (pin "1") (pinfunction "1_1") (pintype "passive"))
    )
    (net (code "125") (name "unconnected-(J114-Pad2)") (class "Default")
      (node (ref "J114") (pin "2") (pinfunction "2_2") (pintype "passive"))
    )
    (net (code "126") (name "unconnected-(J114-Pad3)") (class "Default")
      (node (ref "J114") (pin "3") (pinfunction "3_3") (pintype "passive"))
    )
    (net (code "127") (name "unconnected-(J114-Pad4)") (class "Default")
      (node (ref "J114") (pin "4") (pinfunction "4_4") (pintype "passive"))
    )
    (net (code "128") (name "unconnected-(J114-Pad5)") (class "Default")
      (node (ref "J114") (pin "5") (pinfunction "5_5") (pintype "passive"))
    )
    (net (code "129") (name "unconnected-(J114-Pad6)") (class "Default")
      (node (ref "J114") (pin "6") (pinfunction "6_6") (pintype "passive"))
    )
  )
)
